# Connectivity.net
KiCad netlist of a schematic drawn in Altium Designer
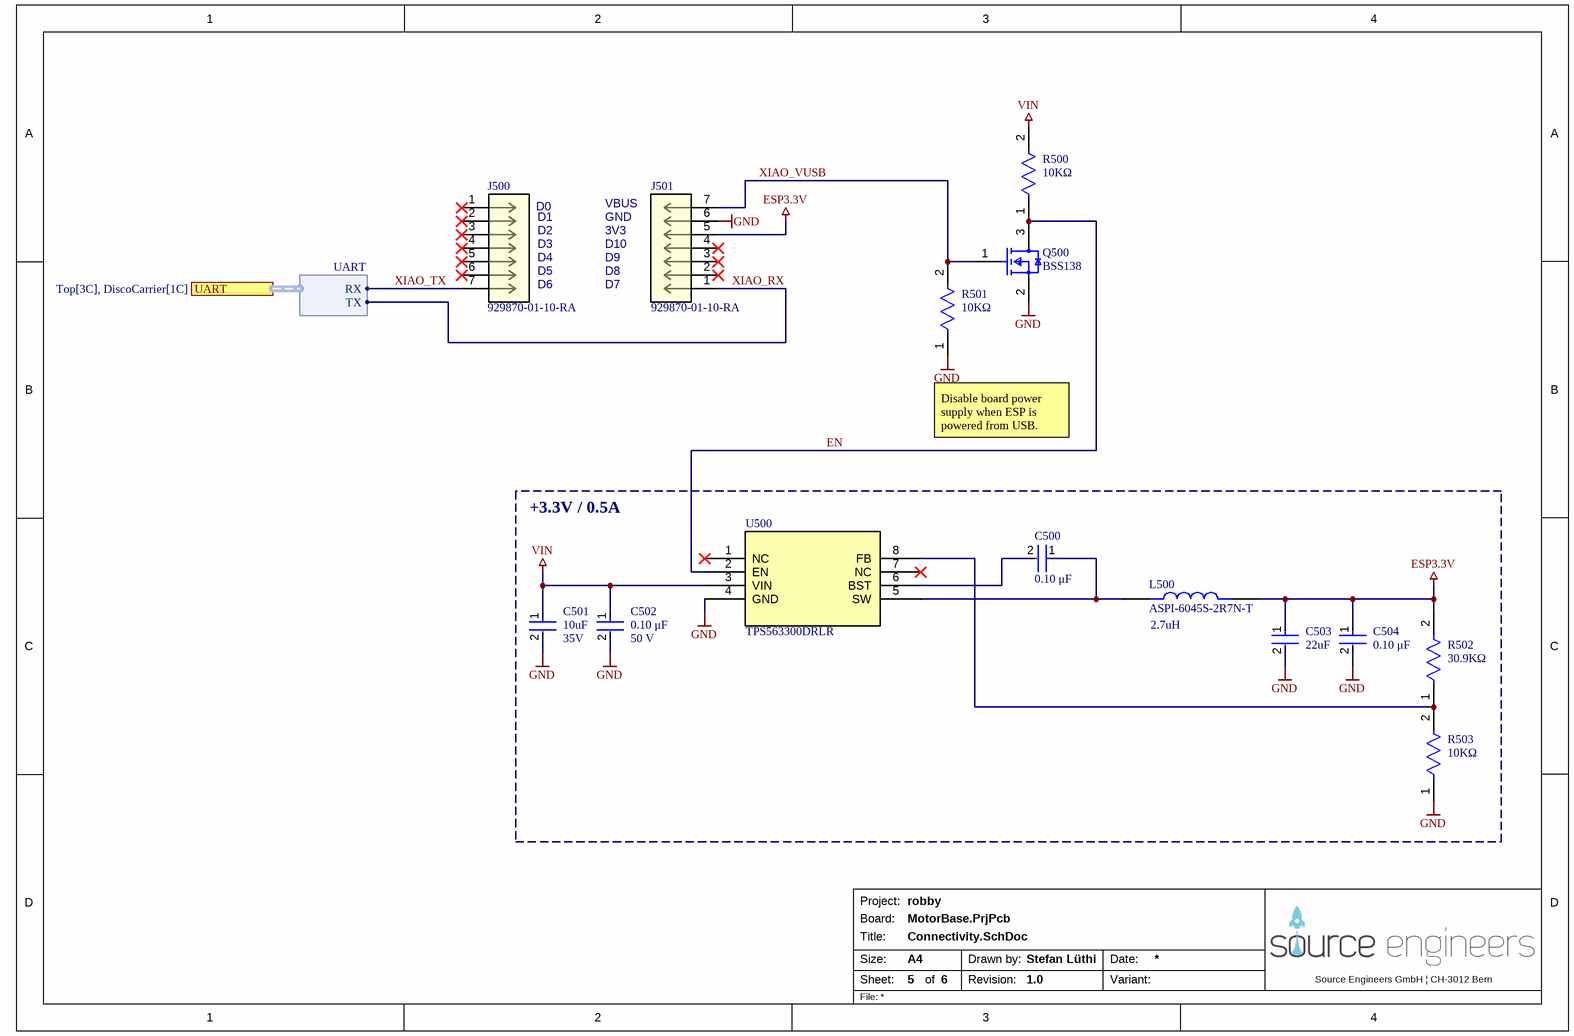
[diagram p0: Connectivity.SchDoc]

(export (version "E")
  (design (tool "Eeschema 10.0.6"))
  (components
    (comp (ref "C500")
      (value "0.10 μF")
      (footprint "FP-C0603C-CF-MFG")
      (description "CAP CER 0.1UF 50V 20% X7R 0603")
      (fields
        (field (name "MANUFACTURER PART NUMBER") "C0603C104M5RACTU")
        (field (name "MANUFACTURER") "KEMET")
      )
      (libsource (lib "Altium Content Vault") (part "b4654b650e69147ec39a6b967a45e02"))
    )
    (comp (ref "C501")
      (value "GRT31CR6YA106KE01L")
      (footprint "FP-GRT31C-0_2-IPC_A")
      (description "Multi-Layer Ceramic Capacitor 10uF 35V X5R ±10% 1206 Emboss T/R")
      (fields
        (field (name "CAPACITANCE") "10uF")
        (field (name "TOLERANCE") "10%")
        (field (name "VOLTAGE RATING") "35V")
      )
      (libsource (lib "Altium Content Vault") (part "02cd4be3c70576c341d710602a673aa"))
    )
    (comp (ref "C502")
      (value "0.10 μF")
      (footprint "FP-C0603C-CF-MFG")
      (description "CAP CER 0.1UF 50V 20% X7R 0603")
      (fields
        (field (name "VOLTAGE RATING") "50 V")
        (field (name "MANUFACTURER PART NUMBER") "C0603C104M5RACTU")
        (field (name "MANUFACTURER") "KEMET")
      )
      (libsource (lib "Altium Content Vault") (part "b4654b650e69147ec39a6b967a45e02"))
    )
    (comp (ref "C503")
      (value "GRM319R61C226ME15D")
      (footprint "FP-GRM319-0_15-IPC_C")
      (description "Chip Multilayer Ceramic Capacitors for General Purpose, 1206, 22uF, X5R, 15%, 20%, 16V")
      (fields (field (name "TOLERANCE") "20%") (field (name "CAPACITANCE") "22uF"))
      (libsource (lib "Altium Content Vault") (part "b4654b650e69147ec39a6b967a45e02"))
    )
    (comp (ref "C504")
      (value "0.10 μF")
      (footprint "FP-C0603C-CF-MFG")
      (description "CAP CER 0.1UF 50V 20% X7R 0603")
      (fields
        (field (name "MANUFACTURER PART NUMBER") "C0603C104M5RACTU")
        (field (name "MANUFACTURER") "KEMET")
      )
      (libsource (lib "Altium Content Vault") (part "b4654b650e69147ec39a6b967a45e02"))
    )
    (comp (ref "J500")
      (value "929870-01-10-RA")
      (footprint "CONN_929870-01-07-RA_3MM")
      (description "No Description Available")
      (fields (field (name "COPYRIGHT") "Copyright (C) 2025 Ultra Librarian. All rights reserved."))
      (libsource (lib "") (part "929870-01-10-RA_1"))
    )
    (comp (ref "J501")
      (value "929870-01-10-RA")
      (footprint "CONN_929870-01-07-RA_3MM")
      (description "No Description Available")
      (fields (field (name "COPYRIGHT") "Copyright (C) 2025 Ultra Librarian. All rights reserved."))
      (libsource (lib "robby") (part "929870-01-10-RA"))
    )
    (comp (ref "L500")
      (value "ASPI-6045S-2R7N-T")
      (footprint "IND_ASPI-6045S-2R7N-T")
      (fields (field (name "ALTIUM_VALUE") "2.7uH"))
      (libsource (lib "robby") (part "ASPI-6045S-2R7N-T"))
    )
    (comp (ref "Q500")
      (value "BSS138")
      (footprint "FP-318-08-IPC_B")
      (description "MOSFET N-CH 50V 220MA SOT-23")
      (libsource (lib "Altium Content Vault") (part "3b9c635fedb024a5347a57b145af9cc"))
    )
    (comp (ref "R500")
      (value "10KΩ")
      (footprint "FP-RT0603-MFG")
      (description "RES SMD 10K OHM 1% 1/10W 0603")
      (fields
        (field (name "MANUFACTURER") "Yageo")
        (field (name "OCTOPART") "https://octopart.com/rt0603fre0710kl-yageo-40009243")
      )
      (libsource (lib "Altium Content Vault") (part "1029c3af85768c4190bb7ad29bc67b5"))
    )
    (comp (ref "R501")
      (value "10KΩ")
      (footprint "FP-RT0603-MFG")
      (description "RES SMD 10K OHM 1% 1/10W 0603")
      (fields
        (field (name "MANUFACTURER") "Yageo")
        (field (name "OCTOPART") "https://octopart.com/rt0603fre0710kl-yageo-40009243")
      )
      (libsource (lib "Altium Content Vault") (part "1029c3af85768c4190bb7ad29bc67b5"))
    )
    (comp (ref "R502")
      (value "RT0603FRE0730K9L")
      (footprint "FP-RT0603-MFG")
      (description "RES SMD 30.9K OHM 1% 1/10W 0603")
      (fields
        (field (name "OCTOPART") "https://octopart.com/rt0603fre0730k9l-yageo-1413622")
        (field (name "RESISTANCE") "30.9KΩ")
        (field (name "MANUFACTURER") "Yageo")
      )
      (libsource (lib "Altium Content Vault") (part "1029c3af85768c4190bb7ad29bc67b5"))
    )
    (comp (ref "R503")
      (value "10KΩ")
      (footprint "FP-RT0603-MFG")
      (description "RES SMD 10K OHM 1% 1/10W 0603")
      (fields
        (field (name "MANUFACTURER") "Yageo")
        (field (name "OCTOPART") "https://octopart.com/rt0603fre0710kl-yageo-40009243")
      )
      (libsource (lib "Altium Content Vault") (part "1029c3af85768c4190bb7ad29bc67b5"))
    )
    (comp (ref "U500")
      (value "TPS563300DRLR")
      (footprint "SOT5X3-8_DRL_TEX")
      (description "3.8-V to 28-V Input, 3-A synchronous buck converter in SOT-583 package 8-SOT-5X3 -40 to 150")
      (fields (field (name "COPYRIGHT") "Copyright (C) 2025 Ultra Librarian. All rights reserved."))
      (libsource (lib "robby") (part "TPS563300DRLR"))
    )
  )
  (nets
    (net (code "2") (name "/EN") (class "Default")
      (node (ref "Q500") (pin "3") (pinfunction "D_3") (pintype "passive"))
      (node (ref "R500") (pin "1") (pinfunction "1_1") (pintype "passive"))
      (node (ref "U500") (pin "2") (pinfunction "EN_2") (pintype "passive"))
    )
    (net (code "3") (name "/XIAO_RX") (class "Default")
      (node (ref "J501") (pin "1") (pinfunction "1_1") (pintype "passive"))
    )
    (net (code "4") (name "/XIAO_TX") (class "Default")
      (node (ref "J500") (pin "7") (pinfunction "7_7") (pintype "passive"))
    )
    (net (code "5") (name "/XIAO_VUSB") (class "Default")
      (node (ref "J501") (pin "7") (pinfunction "7_7") (pintype "passive"))
      (node (ref "Q500") (pin "1") (pinfunction "G_1") (pintype "passive"))
      (node (ref "R501") (pin "2") (pinfunction "2_2") (pintype "passive"))
    )
    (net (code "7") (name "ESP3.3V") (class "Default")
      (node (ref "C503") (pin "1") (pinfunction "1_1") (pintype "passive"))
      (node (ref "C504") (pin "1") (pinfunction "1_1") (pintype "passive"))
      (node (ref "J501") (pin "5") (pinfunction "5_5") (pintype "passive"))
      (node (ref "L500") (pin "2") (pinfunction "2_2") (pintype "passive"))
      (node (ref "R502") (pin "2") (pinfunction "2_2") (pintype "passive"))
    )
    (net (code "8") (name "GND") (class "Default")
      (node (ref "C501") (pin "2") (pinfunction "2_2") (pintype "passive"))
      (node (ref "C502") (pin "2") (pinfunction "2_2") (pintype "passive"))
      (node (ref "C503") (pin "2") (pinfunction "2_2") (pintype "passive"))
      (node (ref "C504") (pin "2") (pinfunction "2_2") (pintype "passive"))
      (node (ref "J501") (pin "6") (pinfunction "6_6") (pintype "passive"))
      (node (ref "Q500") (pin "2") (pinfunction "S_2") (pintype "passive"))
      (node (ref "R501") (pin "1") (pinfunction "1_1") (pintype "passive"))
      (node (ref "R503") (pin "1") (pinfunction "1_1") (pintype "passive"))
      (node (ref "U500") (pin "4") (pinfunction "GND_4") (pintype "power_in"))
    )
    (net (code "9") (name "Net-(U500-BST)") (class "Default")
      (node (ref "C500") (pin "2") (pinfunction "2_2") (pintype "passive"))
      (node (ref "U500") (pin "6") (pinfunction "BST_6") (pintype "power_in"))
    )
    (net (code "10") (name "Net-(U500-FB)") (class "Default")
      (node (ref "R502") (pin "1") (pinfunction "1_1") (pintype "passive"))
      (node (ref "R503") (pin "2") (pinfunction "2_2") (pintype "passive"))
      (node (ref "U500") (pin "8") (pinfunction "FB_8") (pintype "passive"))
    )
    (net (code "11") (name "Net-(U500-SW)") (class "Default")
      (node (ref "C500") (pin "1") (pinfunction "1_1") (pintype "passive"))
      (node (ref "L500") (pin "1") (pinfunction "1_1") (pintype "passive"))
      (node (ref "U500") (pin "5") (pinfunction "SW_5") (pintype "power_in"))
    )
    (net (code "12") (name "VIN") (class "Default")
      (node (ref "C501") (pin "1") (pinfunction "1_1") (pintype "passive"))
      (node (ref "C502") (pin "1") (pinfunction "1_1") (pintype "passive"))
      (node (ref "R500") (pin "2") (pinfunction "2_2") (pintype "passive"))
      (node (ref "U500") (pin "3") (pinfunction "VIN_3") (pintype "power_in"))
    )
    (net (code "13") (name "unconnected-(J500-Pad1)") (class "Default")
      (node (ref "J500") (pin "1") (pinfunction "1_1") (pintype "passive+no_connect"))
    )
    (net (code "14") (name "unconnected-(J500-Pad2)") (class "Default")
      (node (ref "J500") (pin "2") (pinfunction "2_2") (pintype "passive+no_connect"))
    )
    (net (code "15") (name "unconnected-(J500-Pad3)") (class "Default")
      (node (ref "J500") (pin "3") (pinfunction "3_3") (pintype "passive+no_connect"))
    )
    (net (code "16") (name "unconnected-(J500-Pad4)") (class "Default")
      (node (ref "J500") (pin "4") (pinfunction "4_4") (pintype "passive+no_connect"))
    )
    (net (code "17") (name "unconnected-(J500-Pad5)") (class "Default")
      (node (ref "J500") (pin "5") (pinfunction "5_5") (pintype "passive+no_connect"))
    )
    (net (code "18") (name "unconnected-(J500-Pad6)") (class "Default")
      (node (ref "J500") (pin "6") (pinfunction "6_6") (pintype "passive+no_connect"))
    )
    (net (code "19") (name "unconnected-(J501-Pad2)") (class "Default")
      (node (ref "J501") (pin "2") (pinfunction "2_2") (pintype "passive+no_connect"))
    )
    (net (code "20") (name "unconnected-(J501-Pad3)") (class "Default")
      (node (ref "J501") (pin "3") (pinfunction "3_3") (pintype "passive+no_connect"))
    )
    (net (code "21") (name "unconnected-(J501-Pad4)") (class "Default")
      (node (ref "J501") (pin "4") (pinfunction "4_4") (pintype "passive+no_connect"))
    )
    (net (code "22") (name "unconnected-(U500-NC-Pad1)") (class "Default")
      (node (ref "U500") (pin "1") (pinfunction "NC_1") (pintype "passive+no_connect"))
    )
    (net (code "23") (name "unconnected-(U500-NC-Pad7)") (class "Default")
      (node (ref "U500") (pin "7") (pinfunction "NC_7") (pintype "passive+no_connect"))
    )
  )
)
